# Interface.net
KiCad netlist of a schematic drawn in Altium Designer
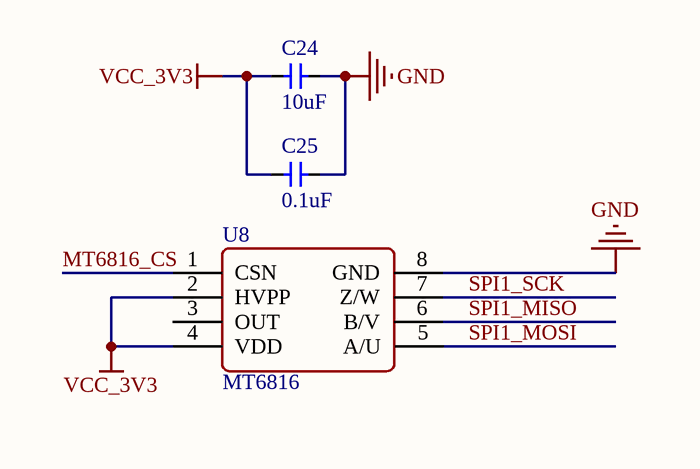
[diagram p0: Interface.SchDoc]

(export (version "E")
  (design (tool "Eeschema 10.0.6"))
  (components
    (comp (ref "C24")
      (value "10uF")
      (footprint "CAP_0402")
      (description "Capacitor")
      (libsource (lib "MyPcbLib") (part "电容-0402"))
    )
    (comp (ref "C25")
      (value "0.1uF")
      (footprint "CAP_0402")
      (description "Capacitor")
      (libsource (lib "MyPcbLib") (part "电容-0402"))
    )
    (comp (ref "U8")
      (value "MT6816")
      (footprint "SO-8")
      (description "Magnetic Position Sensor")
      (libsource (lib "MyPcbLib") (part "MT6816"))
    )
  )
  (nets
    (net (code "1") (name "/MT6816_CS") (class "Default")
      (node (ref "U8") (pin "1") (pinfunction "CSN_1") (pintype "passive"))
    )
    (net (code "2") (name "/SPI1_MISO") (class "Default")
      (node (ref "U8") (pin "6") (pinfunction "B/V_6") (pintype "passive"))
    )
    (net (code "3") (name "/SPI1_MOSI") (class "Default")
      (node (ref "U8") (pin "5") (pinfunction "A/U_5") (pintype "passive"))
    )
    (net (code "4") (name "/SPI1_SCK") (class "Default")
      (node (ref "U8") (pin "7") (pinfunction "Z/W_7") (pintype "passive"))
    )
    (net (code "5") (name "GND") (class "Default")
      (node (ref "C24") (pin "1") (pinfunction "1_1") (pintype "passive"))
      (node (ref "C25") (pin "1") (pinfunction "1_1") (pintype "passive"))
      (node (ref "U8") (pin "8") (pinfunction "GND_8") (pintype "passive"))
    )
    (net (code "6") (name "VCC_3V3") (class "Default")
      (node (ref "C24") (pin "2") (pinfunction "2_2") (pintype "passive"))
      (node (ref "C25") (pin "2") (pinfunction "2_2") (pintype "passive"))
      (node (ref "U8") (pin "2") (pinfunction "HVPP_2") (pintype "passive"))
      (node (ref "U8") (pin "4") (pinfunction "VDD_4") (pintype "passive"))
    )
    (net (code "7") (name "unconnected-(U8-OUT-Pad3)") (class "Default")
      (node (ref "U8") (pin "3") (pinfunction "OUT_3") (pintype "passive"))
    )
  )
)
